# control_panel.net
KiCad netlist of a schematic drawn in EAGLE
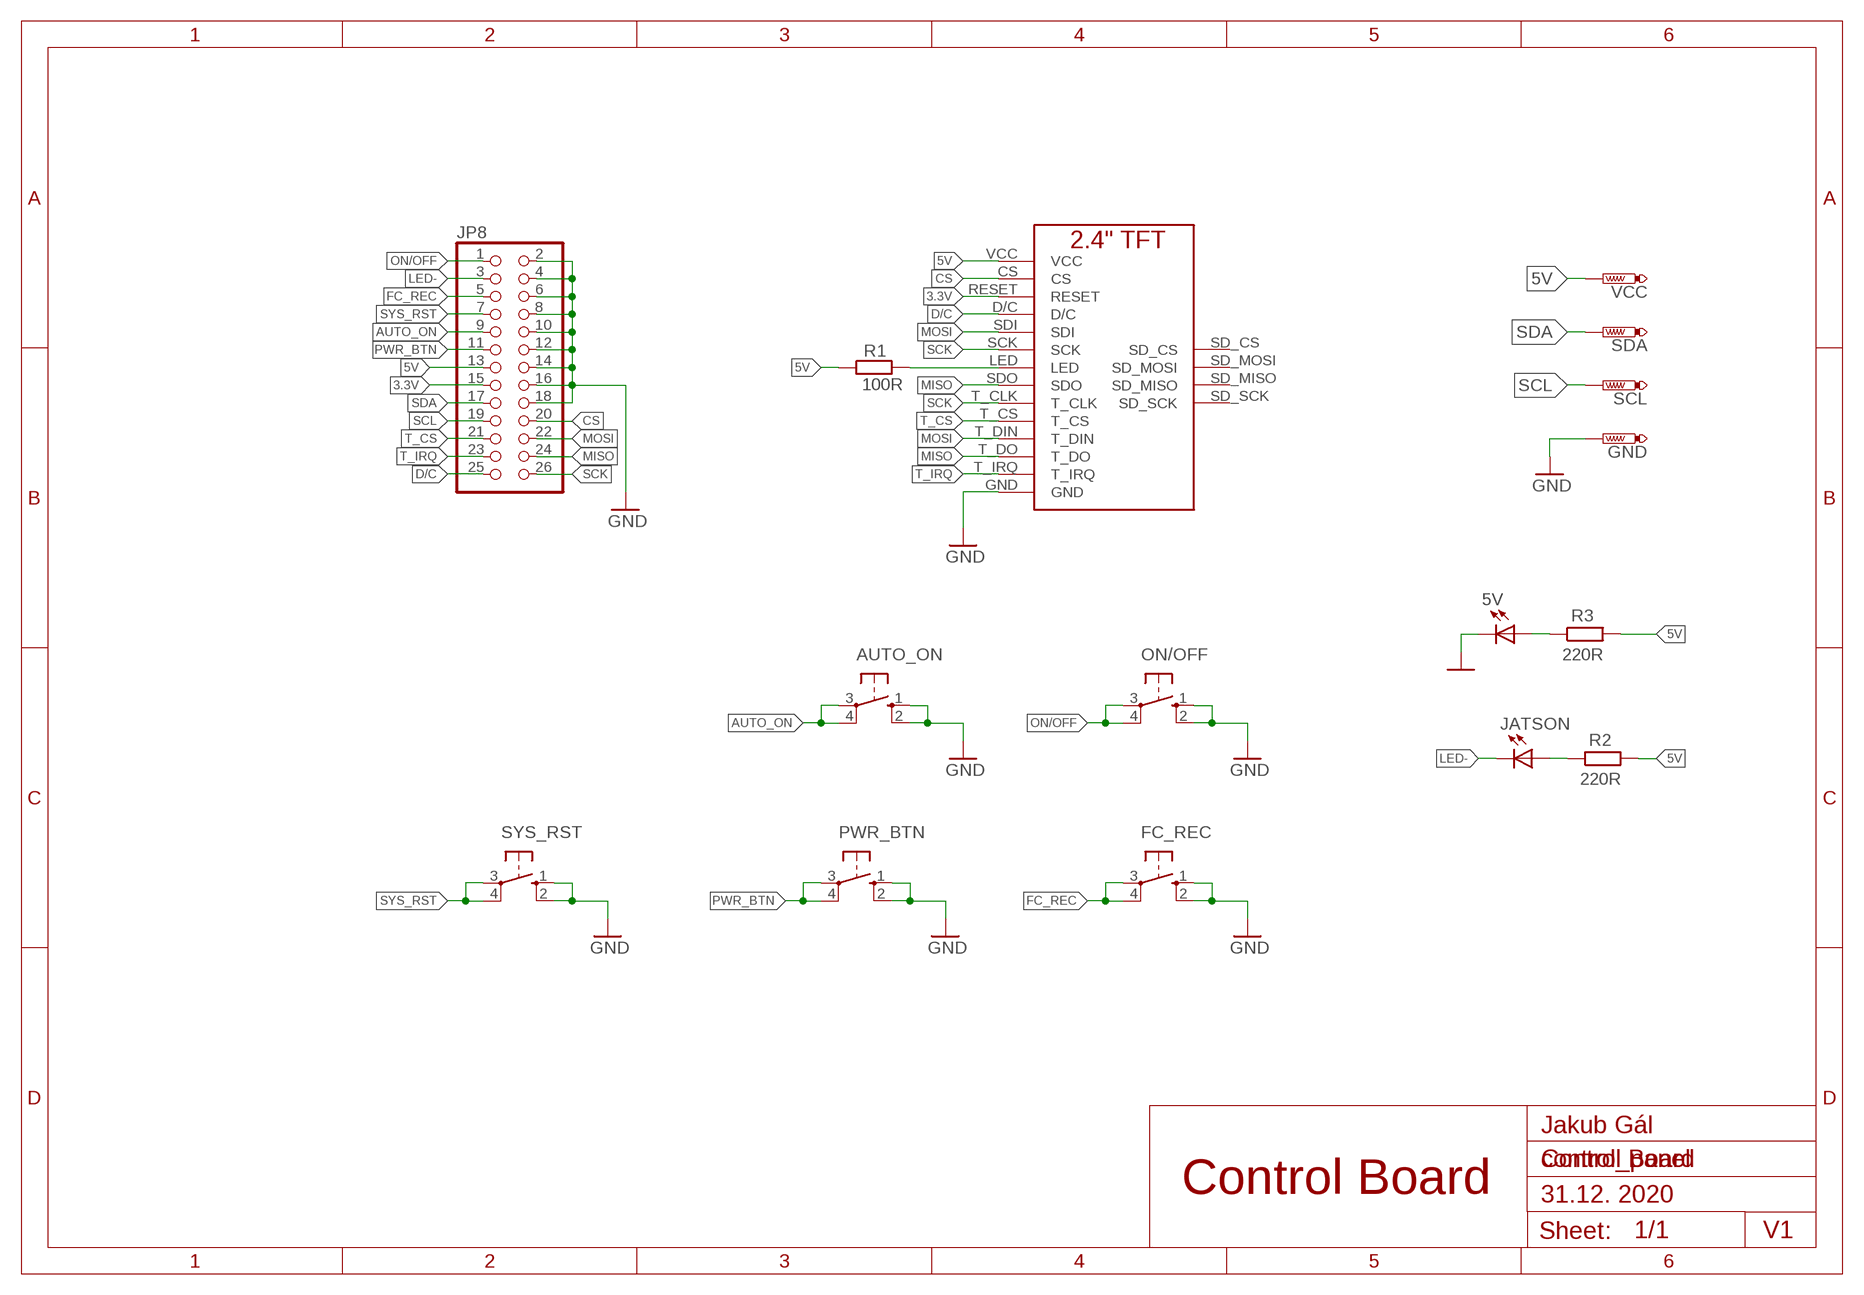
[diagram p0: schematic, sheet 1]

(export (version "E")
  (design (tool "Eeschema 10.0.6"))
  (components
    (comp (ref "5V")
      (value "LEDCHIPLED_0603")
      (footprint "eagle-import:CHIPLED_0603")
      (libsource (lib "eagle-import") (part "LEDCHIPLED_0603"))
    )
    (comp (ref "AUTO_ON")
      (value "10-XX")
      (footprint "eagle-import:B3F-10XX")
      (fields (field (name "MPN") "B3F-1000"))
      (libsource (lib "eagle-import") (part "10-XX"))
    )
    (comp (ref "FC_REC")
      (value "10-XX")
      (footprint "eagle-import:B3F-10XX")
      (fields (field (name "MPN") "B3F-1000"))
      (libsource (lib "eagle-import") (part "10-XX"))
    )
    (comp (ref "GND")
      (value "PTR1TP20R")
      (footprint "eagle-import:TP20R")
      (libsource (lib "eagle-import") (part "PTR1TP20R"))
    )
    (comp (ref "JATSON")
      (value "LEDCHIPLED_0603")
      (footprint "eagle-import:CHIPLED_0603")
      (libsource (lib "eagle-import") (part "LEDCHIPLED_0603"))
    )
    (comp (ref "JP8")
      (value "PINHD-2X13_2.54")
      (footprint "eagle-import:2X13")
      (libsource (lib "eagle-import") (part "PINHD-2X13_2.54"))
    )
    (comp (ref "ON/OFF")
      (value "10-XX")
      (footprint "eagle-import:B3F-10XX")
      (fields (field (name "MPN") "B3F-1000"))
      (libsource (lib "eagle-import") (part "10-XX"))
    )
    (comp (ref "PWR_BTN")
      (value "10-XX")
      (footprint "eagle-import:B3F-10XX")
      (fields (field (name "MPN") "B3F-1000"))
      (libsource (lib "eagle-import") (part "10-XX"))
    )
    (comp (ref "R1")
      (value "100R")
      (footprint "eagle-import:R0603")
      (libsource (lib "eagle-import") (part "R-EU_R0603"))
    )
    (comp (ref "R2")
      (value "220R")
      (footprint "eagle-import:R0603")
      (libsource (lib "eagle-import") (part "R-EU_R0603"))
    )
    (comp (ref "R3")
      (value "220R")
      (footprint "eagle-import:R0603")
      (libsource (lib "eagle-import") (part "R-EU_R0603"))
    )
    (comp (ref "SCL")
      (value "PTR1TP20R")
      (footprint "eagle-import:TP20R")
      (libsource (lib "eagle-import") (part "PTR1TP20R"))
    )
    (comp (ref "SDA")
      (value "PTR1TP20R")
      (footprint "eagle-import:TP20R")
      (libsource (lib "eagle-import") (part "PTR1TP20R"))
    )
    (comp (ref "SYS_RST")
      (value "10-XX")
      (footprint "eagle-import:B3F-10XX")
      (fields (field (name "MPN") "B3F-1000"))
      (libsource (lib "eagle-import") (part "10-XX"))
    )
    (comp (ref "U$1")
      (value "2.4\"TFT")
      (footprint "eagle-import:TFT_2.4_")
      (libsource (lib "eagle-import") (part "2.4{dblquote}TFT"))
    )
    (comp (ref "VCC")
      (value "PTR1TP20R")
      (footprint "eagle-import:TP20R")
      (libsource (lib "eagle-import") (part "PTR1TP20R"))
    )
  )
  (nets
    (net (code "1") (name "3.3V") (class "Default")
      (node (ref "JP8") (pin "15") (pinfunction "15_15") (pintype "passive"))
      (node (ref "U$1") (pin "RESET") (pinfunction "RESET_RESET") (pintype "bidirectional"))
    )
    (net (code "2") (name "5V") (class "Default")
      (node (ref "JP8") (pin "13") (pinfunction "13_13") (pintype "passive"))
      (node (ref "R1") (pin "1") (pinfunction "1_1") (pintype "passive"))
      (node (ref "R2") (pin "2") (pinfunction "2_2") (pintype "passive"))
      (node (ref "R3") (pin "2") (pinfunction "2_2") (pintype "passive"))
      (node (ref "U$1") (pin "VCC") (pinfunction "VCC_VCC") (pintype "bidirectional"))
      (node (ref "VCC") (pin "TP") (pinfunction "TP_TP") (pintype "input"))
    )
    (net (code "3") (name "AUTO_ON") (class "Default")
      (node (ref "AUTO_ON") (pin "3") (pinfunction "P_3") (pintype "passive"))
      (node (ref "AUTO_ON") (pin "4") (pinfunction "P1_4") (pintype "passive"))
      (node (ref "JP8") (pin "9") (pinfunction "9_9") (pintype "passive"))
    )
    (net (code "4") (name "CS") (class "Default")
      (node (ref "JP8") (pin "20") (pinfunction "20_20") (pintype "passive"))
      (node (ref "U$1") (pin "CS") (pinfunction "CS_CS") (pintype "bidirectional"))
    )
    (net (code "5") (name "D{slash}C") (class "Default")
      (node (ref "JP8") (pin "25") (pinfunction "25_25") (pintype "passive"))
      (node (ref "U$1") (pin "D/C") (pinfunction "D/C_D/C") (pintype "bidirectional"))
    )
    (net (code "6") (name "FC_REC") (class "Default")
      (node (ref "FC_REC") (pin "3") (pinfunction "P_3") (pintype "passive"))
      (node (ref "FC_REC") (pin "4") (pinfunction "P1_4") (pintype "passive"))
      (node (ref "JP8") (pin "5") (pinfunction "5_5") (pintype "passive"))
    )
    (net (code "7") (name "GND") (class "Default")
      (node (ref "5V") (pin "C") (pinfunction "C_C") (pintype "passive"))
      (node (ref "AUTO_ON") (pin "1") (pinfunction "S_1") (pintype "passive"))
      (node (ref "AUTO_ON") (pin "2") (pinfunction "S1_2") (pintype "passive"))
      (node (ref "FC_REC") (pin "1") (pinfunction "S_1") (pintype "passive"))
      (node (ref "FC_REC") (pin "2") (pinfunction "S1_2") (pintype "passive"))
      (node (ref "GND") (pin "TP") (pinfunction "TP_TP") (pintype "input"))
      (node (ref "JP8") (pin "10") (pinfunction "10_10") (pintype "passive"))
      (node (ref "JP8") (pin "12") (pinfunction "12_12") (pintype "passive"))
      (node (ref "JP8") (pin "14") (pinfunction "14_14") (pintype "passive"))
      (node (ref "JP8") (pin "16") (pinfunction "16_16") (pintype "passive"))
      (node (ref "JP8") (pin "18") (pinfunction "18_18") (pintype "passive"))
      (node (ref "JP8") (pin "2") (pinfunction "2_2") (pintype "passive"))
      (node (ref "JP8") (pin "4") (pinfunction "4_4") (pintype "passive"))
      (node (ref "JP8") (pin "6") (pinfunction "6_6") (pintype "passive"))
      (node (ref "JP8") (pin "8") (pinfunction "8_8") (pintype "passive"))
      (node (ref "ON/OFF") (pin "1") (pinfunction "S_1") (pintype "passive"))
      (node (ref "ON/OFF") (pin "2") (pinfunction "S1_2") (pintype "passive"))
      (node (ref "PWR_BTN") (pin "1") (pinfunction "S_1") (pintype "passive"))
      (node (ref "PWR_BTN") (pin "2") (pinfunction "S1_2") (pintype "passive"))
      (node (ref "SYS_RST") (pin "1") (pinfunction "S_1") (pintype "passive"))
      (node (ref "SYS_RST") (pin "2") (pinfunction "S1_2") (pintype "passive"))
      (node (ref "U$1") (pin "GND") (pinfunction "GND_GND") (pintype "bidirectional"))
    )
    (net (code "8") (name "LED-") (class "Default")
      (node (ref "JATSON") (pin "C") (pinfunction "C_C") (pintype "passive"))
      (node (ref "JP8") (pin "3") (pinfunction "3_3") (pintype "passive"))
    )
    (net (code "9") (name "MISO") (class "Default")
      (node (ref "JP8") (pin "24") (pinfunction "24_24") (pintype "passive"))
      (node (ref "U$1") (pin "SDO") (pinfunction "SDO_SDO") (pintype "bidirectional"))
      (node (ref "U$1") (pin "T_DO") (pinfunction "T_DO_T_DO") (pintype "bidirectional"))
    )
    (net (code "10") (name "MOSI") (class "Default")
      (node (ref "JP8") (pin "22") (pinfunction "22_22") (pintype "passive"))
      (node (ref "U$1") (pin "SDI") (pinfunction "SDI_SDI") (pintype "bidirectional"))
      (node (ref "U$1") (pin "T_DIN") (pinfunction "T_DIN_T_DIN") (pintype "bidirectional"))
    )
    (net (code "11") (name "Net-(5V-PadA)") (class "Default")
      (node (ref "5V") (pin "A") (pinfunction "A_A") (pintype "passive"))
      (node (ref "R3") (pin "1") (pinfunction "1_1") (pintype "passive"))
    )
    (net (code "12") (name "Net-(JATSON-PadA)") (class "Default")
      (node (ref "JATSON") (pin "A") (pinfunction "A_A") (pintype "passive"))
      (node (ref "R2") (pin "1") (pinfunction "1_1") (pintype "passive"))
    )
    (net (code "13") (name "Net-(R1-Pad2)") (class "Default")
      (node (ref "R1") (pin "2") (pinfunction "2_2") (pintype "passive"))
      (node (ref "U$1") (pin "LED") (pinfunction "LED_LED") (pintype "bidirectional"))
    )
    (net (code "14") (name "ON{slash}OFF") (class "Default")
      (node (ref "JP8") (pin "1") (pinfunction "1_1") (pintype "passive"))
      (node (ref "ON/OFF") (pin "3") (pinfunction "P_3") (pintype "passive"))
      (node (ref "ON/OFF") (pin "4") (pinfunction "P1_4") (pintype "passive"))
    )
    (net (code "15") (name "PWR_BTN") (class "Default")
      (node (ref "JP8") (pin "11") (pinfunction "11_11") (pintype "passive"))
      (node (ref "PWR_BTN") (pin "3") (pinfunction "P_3") (pintype "passive"))
      (node (ref "PWR_BTN") (pin "4") (pinfunction "P1_4") (pintype "passive"))
    )
    (net (code "16") (name "SCK") (class "Default")
      (node (ref "JP8") (pin "26") (pinfunction "26_26") (pintype "passive"))
      (node (ref "U$1") (pin "SCK") (pinfunction "SCK_SCK") (pintype "bidirectional"))
      (node (ref "U$1") (pin "T_CLK") (pinfunction "T_CLK_T_CLK") (pintype "bidirectional"))
    )
    (net (code "17") (name "SCL") (class "Default")
      (node (ref "JP8") (pin "19") (pinfunction "19_19") (pintype "passive"))
      (node (ref "SCL") (pin "TP") (pinfunction "TP_TP") (pintype "input"))
    )
    (net (code "18") (name "SDA") (class "Default")
      (node (ref "JP8") (pin "17") (pinfunction "17_17") (pintype "passive"))
      (node (ref "SDA") (pin "TP") (pinfunction "TP_TP") (pintype "input"))
    )
    (net (code "19") (name "SYS_RST") (class "Default")
      (node (ref "JP8") (pin "7") (pinfunction "7_7") (pintype "passive"))
      (node (ref "SYS_RST") (pin "3") (pinfunction "P_3") (pintype "passive"))
      (node (ref "SYS_RST") (pin "4") (pinfunction "P1_4") (pintype "passive"))
    )
    (net (code "20") (name "T_CS") (class "Default")
      (node (ref "JP8") (pin "21") (pinfunction "21_21") (pintype "passive"))
      (node (ref "U$1") (pin "T_CS") (pinfunction "T_CS_T_CS") (pintype "bidirectional"))
    )
    (net (code "21") (name "T_IRQ") (class "Default")
      (node (ref "JP8") (pin "23") (pinfunction "23_23") (pintype "passive"))
      (node (ref "U$1") (pin "T_IRQ") (pinfunction "T_IRQ_T_IRQ") (pintype "bidirectional"))
    )
    (net (code "22") (name "unconnected-(U$1-PadSD_CS)") (class "Default")
      (node (ref "U$1") (pin "SD_CS") (pinfunction "SD_CS_SD_CS") (pintype "bidirectional"))
    )
    (net (code "23") (name "unconnected-(U$1-PadSD_MISO)") (class "Default")
      (node (ref "U$1") (pin "SD_MISO") (pinfunction "SD_MISO_SD_MISO") (pintype "bidirectional"))
    )
    (net (code "24") (name "unconnected-(U$1-PadSD_MOSI)") (class "Default")
      (node (ref "U$1") (pin "SD_MOSI") (pinfunction "SD_MOSI_SD_MOSI") (pintype "bidirectional"))
    )
    (net (code "25") (name "unconnected-(U$1-PadSD_SCK)") (class "Default")
      (node (ref "U$1") (pin "SD_SCK") (pinfunction "SD_SCK_SD_SCK") (pintype "bidirectional"))
    )
  )
)
